# Output.net
KiCad netlist of a schematic drawn in Altium Designer
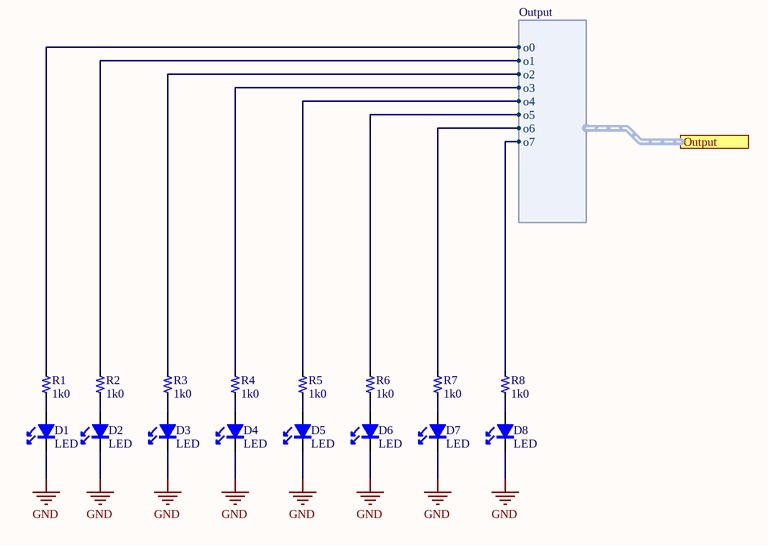
[diagram p0: Output.SchDoc]

(export (version "E")
  (design (tool "Eeschema 10.0.6"))
  (components
    (comp (ref "D1")
      (value "LED")
      (footprint "LED-0805")
      (description "LED - Light-Emitting Diode")
      (libsource (lib "RasUNMSM") (part "LED"))
    )
    (comp (ref "D2")
      (value "LED")
      (footprint "LED-0805")
      (description "LED - Light-Emitting Diode")
      (libsource (lib "RasUNMSM") (part "LED"))
    )
    (comp (ref "D3")
      (value "LED")
      (footprint "LED-0805")
      (description "LED - Light-Emitting Diode")
      (libsource (lib "RasUNMSM") (part "LED"))
    )
    (comp (ref "D4")
      (value "LED")
      (footprint "LED-0805")
      (description "LED - Light-Emitting Diode")
      (libsource (lib "RasUNMSM") (part "LED"))
    )
    (comp (ref "D5")
      (value "LED")
      (footprint "LED-0805")
      (description "LED - Light-Emitting Diode")
      (libsource (lib "RasUNMSM") (part "LED"))
    )
    (comp (ref "D6")
      (value "LED")
      (footprint "LED-0805")
      (description "LED - Light-Emitting Diode")
      (libsource (lib "RasUNMSM") (part "LED"))
    )
    (comp (ref "D7")
      (value "LED")
      (footprint "LED-0805")
      (description "LED - Light-Emitting Diode")
      (libsource (lib "RasUNMSM") (part "LED"))
    )
    (comp (ref "D8")
      (value "LED")
      (footprint "LED-0805")
      (description "LED - Light-Emitting Diode")
      (libsource (lib "RasUNMSM") (part "LED"))
    )
    (comp (ref "R1")
      (value "1k0")
      (footprint "R0805")
      (description "Single resistor")
      (fields (field (name "POWER") "0.125W"))
      (libsource (lib "RasUNMSM") (part "Resistor"))
    )
    (comp (ref "R2")
      (value "1k0")
      (footprint "R0805")
      (description "Single resistor")
      (fields (field (name "POWER") "0.125W"))
      (libsource (lib "RasUNMSM") (part "Resistor"))
    )
    (comp (ref "R3")
      (value "1k0")
      (footprint "R0805")
      (description "Single resistor")
      (fields (field (name "POWER") "0.125W"))
      (libsource (lib "RasUNMSM") (part "Resistor"))
    )
    (comp (ref "R4")
      (value "1k0")
      (footprint "R0805")
      (description "Single resistor")
      (fields (field (name "POWER") "0.125W"))
      (libsource (lib "RasUNMSM") (part "Resistor"))
    )
    (comp (ref "R5")
      (value "1k0")
      (footprint "R0805")
      (description "Single resistor")
      (fields (field (name "POWER") "0.125W"))
      (libsource (lib "RasUNMSM") (part "Resistor"))
    )
    (comp (ref "R6")
      (value "1k0")
      (footprint "R0805")
      (description "Single resistor")
      (fields (field (name "POWER") "0.125W"))
      (libsource (lib "RasUNMSM") (part "Resistor"))
    )
    (comp (ref "R7")
      (value "1k0")
      (footprint "R0805")
      (description "Single resistor")
      (fields (field (name "POWER") "0.125W"))
      (libsource (lib "RasUNMSM") (part "Resistor"))
    )
    (comp (ref "R8")
      (value "1k0")
      (footprint "R0805")
      (description "Single resistor")
      (fields (field (name "POWER") "0.125W"))
      (libsource (lib "RasUNMSM") (part "Resistor"))
    )
  )
  (nets
    (net (code "2") (name "/o0") (class "Default")
      (node (ref "R1") (pin "2") (pinfunction "2_2") (pintype "passive"))
    )
    (net (code "3") (name "/o1") (class "Default")
      (node (ref "R2") (pin "2") (pinfunction "2_2") (pintype "passive"))
    )
    (net (code "4") (name "/o2") (class "Default")
      (node (ref "R3") (pin "2") (pinfunction "2_2") (pintype "passive"))
    )
    (net (code "5") (name "/o3") (class "Default")
      (node (ref "R4") (pin "2") (pinfunction "2_2") (pintype "passive"))
    )
    (net (code "6") (name "/o4") (class "Default")
      (node (ref "R5") (pin "2") (pinfunction "2_2") (pintype "passive"))
    )
    (net (code "7") (name "/o5") (class "Default")
      (node (ref "R6") (pin "2") (pinfunction "2_2") (pintype "passive"))
    )
    (net (code "8") (name "/o6") (class "Default")
      (node (ref "R7") (pin "2") (pinfunction "2_2") (pintype "passive"))
    )
    (net (code "9") (name "/o7") (class "Default")
      (node (ref "R8") (pin "2") (pinfunction "2_2") (pintype "passive"))
    )
    (net (code "11") (name "GND") (class "Default")
      (node (ref "D1") (pin "1") (pinfunction "1_1") (pintype "passive"))
      (node (ref "D2") (pin "1") (pinfunction "1_1") (pintype "passive"))
      (node (ref "D3") (pin "1") (pinfunction "1_1") (pintype "passive"))
      (node (ref "D4") (pin "1") (pinfunction "1_1") (pintype "passive"))
      (node (ref "D5") (pin "1") (pinfunction "1_1") (pintype "passive"))
      (node (ref "D6") (pin "1") (pinfunction "1_1") (pintype "passive"))
      (node (ref "D7") (pin "1") (pinfunction "1_1") (pintype "passive"))
      (node (ref "D8") (pin "1") (pinfunction "1_1") (pintype "passive"))
    )
    (net (code "12") (name "Net-(D1-Pad2)") (class "Default")
      (node (ref "D1") (pin "2") (pinfunction "2_2") (pintype "passive"))
      (node (ref "R1") (pin "1") (pinfunction "1_1") (pintype "passive"))
    )
    (net (code "13") (name "Net-(D2-Pad2)") (class "Default")
      (node (ref "D2") (pin "2") (pinfunction "2_2") (pintype "passive"))
      (node (ref "R2") (pin "1") (pinfunction "1_1") (pintype "passive"))
    )
    (net (code "14") (name "Net-(D3-Pad2)") (class "Default")
      (node (ref "D3") (pin "2") (pinfunction "2_2") (pintype "passive"))
      (node (ref "R3") (pin "1") (pinfunction "1_1") (pintype "passive"))
    )
    (net (code "15") (name "Net-(D4-Pad2)") (class "Default")
      (node (ref "D4") (pin "2") (pinfunction "2_2") (pintype "passive"))
      (node (ref "R4") (pin "1") (pinfunction "1_1") (pintype "passive"))
    )
    (net (code "16") (name "Net-(D5-Pad2)") (class "Default")
      (node (ref "D5") (pin "2") (pinfunction "2_2") (pintype "passive"))
      (node (ref "R5") (pin "1") (pinfunction "1_1") (pintype "passive"))
    )
    (net (code "17") (name "Net-(D6-Pad2)") (class "Default")
      (node (ref "D6") (pin "2") (pinfunction "2_2") (pintype "passive"))
      (node (ref "R6") (pin "1") (pinfunction "1_1") (pintype "passive"))
    )
    (net (code "18") (name "Net-(D7-Pad2)") (class "Default")
      (node (ref "D7") (pin "2") (pinfunction "2_2") (pintype "passive"))
      (node (ref "R7") (pin "1") (pinfunction "1_1") (pintype "passive"))
    )
    (net (code "19") (name "Net-(D8-Pad2)") (class "Default")
      (node (ref "D8") (pin "2") (pinfunction "2_2") (pintype "passive"))
      (node (ref "R8") (pin "1") (pinfunction "1_1") (pintype "passive"))
    )
  )
)
